# lcd_arduino_alarm_clock.net
KiCad netlist of a schematic drawn in EAGLE
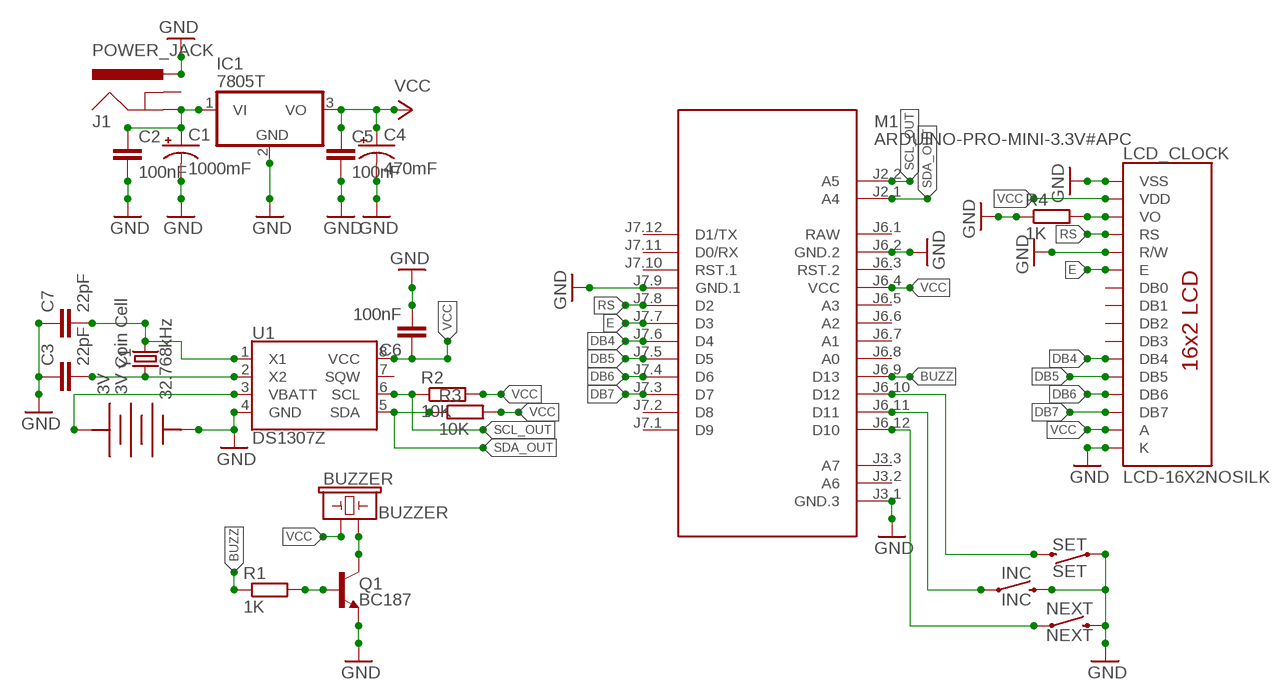
[diagram p0: schematic, sheet 1]

(export (version "E")
  (design (tool "Eeschema 10.0.6"))
  (components
    (comp (ref "3V")
      (value "3V Coin Cell")
      (footprint "eagle-import:FKIT-LIR2450-H")
      (libsource (lib "eagle-import") (part "FKIT-COIN_CELLLIR2450-H"))
    )
    (comp (ref "BUZZER")
      (value "BUZZER")
      (footprint "eagle-import:BUZZER-12MM")
      (libsource (lib "eagle-import") (part "BUZZER-PTH"))
    )
    (comp (ref "C1")
      (value "1000mF")
      (footprint "eagle-import:CPOL-RADIAL-5MM-10MM")
      (libsource (lib "eagle-import") (part "1000UF-RADIAL-5MM-25V-20%"))
    )
    (comp (ref "C2")
      (value "100nF")
      (footprint "eagle-import:0603")
      (libsource (lib "eagle-import") (part "100PF-0603-50V-5%"))
    )
    (comp (ref "C3")
      (value "22pF")
      (footprint "eagle-import:0603")
      (libsource (lib "eagle-import") (part "100PF-0603-50V-5%"))
    )
    (comp (ref "C4")
      (value "470mF")
      (footprint "eagle-import:CPOL-RADIAL-5MM-10MM")
      (libsource (lib "eagle-import") (part "1000UF-RADIAL-5MM-25V-20%"))
    )
    (comp (ref "C5")
      (value "100nF")
      (footprint "eagle-import:0603")
      (libsource (lib "eagle-import") (part "100PF-0603-50V-5%"))
    )
    (comp (ref "C6")
      (value "100nF")
      (footprint "eagle-import:0603")
      (libsource (lib "eagle-import") (part "100PF-0603-50V-5%"))
    )
    (comp (ref "C7")
      (value "22pF")
      (footprint "eagle-import:0603")
      (libsource (lib "eagle-import") (part "100PF-0603-50V-5%"))
    )
    (comp (ref "IC1")
      (value "7805T")
      (footprint "eagle-import:TO220H")
      (libsource (lib "eagle-import") (part "78T05"))
    )
    (comp (ref "INC")
      (value "INC")
      (footprint "eagle-import:TACTILE_SWITCH_PTH_6.0MM")
      (libsource (lib "eagle-import") (part "MOMENTARY-SWITCH-SPST-PTH-6.0MM"))
    )
    (comp (ref "J1")
      (value "POWER_JACK")
      (footprint "eagle-import:POWER_JACK_PTH")
      (libsource (lib "eagle-import") (part "POWER_JACK"))
    )
    (comp (ref "LCD_CLOCK")
      (value "LCD-16X2NOSILK")
      (footprint "eagle-import:LCD-16X2_NOSILK")
      (libsource (lib "eagle-import") (part "LCD-16X2NOSILK"))
    )
    (comp (ref "M1")
      (value "ARDUINO-PRO-MINI-3.3V#APC")
      (footprint "eagle-import:ARDUINO-PRO-MINI#APC")
      (libsource (lib "eagle-import") (part "ARDUINO-PRO-MINI-#APC3.3V"))
    )
    (comp (ref "NEXT")
      (value "NEXT")
      (footprint "eagle-import:TACTILE_SWITCH_PTH_6.0MM")
      (libsource (lib "eagle-import") (part "MOMENTARY-SWITCH-SPST-PTH-6.0MM"))
    )
    (comp (ref "Q1")
      (value "BC187")
      (footprint "eagle-import:TO-92")
      (libsource (lib "eagle-import") (part "TRANS_NPN-2N3904"))
    )
    (comp (ref "R1")
      (value "1K")
      (footprint "eagle-import:0204_5")
      (libsource (lib "eagle-import") (part "R-EU_0204/5"))
    )
    (comp (ref "R2")
      (value "10K")
      (footprint "eagle-import:0204_5")
      (libsource (lib "eagle-import") (part "R-EU_0204/5"))
    )
    (comp (ref "R3")
      (value "10K")
      (footprint "eagle-import:0204_5")
      (libsource (lib "eagle-import") (part "R-EU_0204/5"))
    )
    (comp (ref "R4")
      (value "1K")
      (footprint "eagle-import:0204_5")
      (libsource (lib "eagle-import") (part "R-EU_0204/5"))
    )
    (comp (ref "SET")
      (value "SET")
      (footprint "eagle-import:TACTILE_SWITCH_PTH_6.0MM")
      (libsource (lib "eagle-import") (part "MOMENTARY-SWITCH-SPST-PTH-6.0MM"))
    )
    (comp (ref "U1")
      (value "DS1307Z")
      (footprint "eagle-import:SO08-0.15")
      (libsource (lib "eagle-import") (part "DS1307Z"))
    )
    (comp (ref "Y1")
      (value "32.768kHz")
      (footprint "eagle-import:CRYSTAL-PTH-2X6-CYL")
      (libsource (lib "eagle-import") (part "CRYSTAL-32.768KHZPTH-2X6"))
    )
  )
  (nets
    (net (code "1") (name "/RAW") (class "Default")
      (node (ref "M1") (pin "J6.1") (pinfunction "RAW_J6.1") (pintype "power_in"))
    )
    (net (code "2") (name "BUZZ") (class "Default")
      (node (ref "M1") (pin "J6.9") (pinfunction "D13_J6.9") (pintype "bidirectional"))
      (node (ref "R1") (pin "1") (pinfunction "1_1") (pintype "passive"))
    )
    (net (code "3") (name "DB4") (class "Default")
      (node (ref "LCD_CLOCK") (pin "11") (pinfunction "DB4_11") (pintype "bidirectional"))
      (node (ref "M1") (pin "J7.6") (pinfunction "D4_J7.6") (pintype "bidirectional"))
    )
    (net (code "4") (name "DB5") (class "Default")
      (node (ref "LCD_CLOCK") (pin "12") (pinfunction "DB5_12") (pintype "bidirectional"))
      (node (ref "M1") (pin "J7.5") (pinfunction "D5_J7.5") (pintype "bidirectional"))
    )
    (net (code "5") (name "DB6") (class "Default")
      (node (ref "LCD_CLOCK") (pin "13") (pinfunction "DB6_13") (pintype "bidirectional"))
      (node (ref "M1") (pin "J7.4") (pinfunction "D6_J7.4") (pintype "bidirectional"))
    )
    (net (code "6") (name "DB7") (class "Default")
      (node (ref "LCD_CLOCK") (pin "14") (pinfunction "DB7_14") (pintype "bidirectional"))
      (node (ref "M1") (pin "J7.3") (pinfunction "D7_J7.3") (pintype "bidirectional"))
    )
    (net (code "7") (name "E") (class "Default")
      (node (ref "LCD_CLOCK") (pin "6") (pinfunction "E_6") (pintype "input"))
      (node (ref "M1") (pin "J7.7") (pinfunction "D3_J7.7") (pintype "bidirectional"))
    )
    (net (code "8") (name "GND") (class "Default")
      (node (ref "3V") (pin "NEG") (pinfunction "NEG_NEG") (pintype "bidirectional"))
      (node (ref "C1") (pin "-") (pinfunction "-_-") (pintype "passive"))
      (node (ref "C2") (pin "2") (pinfunction "2_2") (pintype "passive"))
      (node (ref "C3") (pin "1") (pinfunction "1_1") (pintype "passive"))
      (node (ref "C4") (pin "-") (pinfunction "-_-") (pintype "passive"))
      (node (ref "C5") (pin "2") (pinfunction "2_2") (pintype "passive"))
      (node (ref "C6") (pin "2") (pinfunction "2_2") (pintype "passive"))
      (node (ref "C7") (pin "1") (pinfunction "1_1") (pintype "passive"))
      (node (ref "IC1") (pin "2") (pinfunction "GND_2") (pintype "passive"))
      (node (ref "INC") (pin "3") (pinfunction "2_3") (pintype "passive"))
      (node (ref "J1") (pin "PWR") (pinfunction "PWR_PWR") (pintype "bidirectional"))
      (node (ref "LCD_CLOCK") (pin "1") (pinfunction "VSS_1") (pintype "power_in"))
      (node (ref "LCD_CLOCK") (pin "16") (pinfunction "K_16") (pintype "power_in"))
      (node (ref "LCD_CLOCK") (pin "5") (pinfunction "R/W_5") (pintype "input"))
      (node (ref "M1") (pin "J3.1") (pinfunction "GND.3_J3.1") (pintype "bidirectional"))
      (node (ref "M1") (pin "J6.2") (pinfunction "GND.2_J6.2") (pintype "power_in"))
      (node (ref "M1") (pin "J7.9") (pinfunction "GND.1_J7.9") (pintype "power_in"))
      (node (ref "NEXT") (pin "3") (pinfunction "2_3") (pintype "passive"))
      (node (ref "Q1") (pin "1") (pinfunction "E_1") (pintype "passive"))
      (node (ref "R4") (pin "1") (pinfunction "1_1") (pintype "passive"))
      (node (ref "SET") (pin "1") (pinfunction "1_1") (pintype "passive"))
      (node (ref "U1") (pin "4") (pinfunction "GND_4") (pintype "bidirectional"))
    )
    (net (code "9") (name "Net-(BUZZER-2)") (class "Default")
      (node (ref "BUZZER") (pin "-") (pinfunction "2_-") (pintype "passive"))
      (node (ref "Q1") (pin "3") (pinfunction "C_3") (pintype "passive"))
    )
    (net (code "10") (name "Net-(IC1-VI)") (class "Default")
      (node (ref "C1") (pin "+") (pinfunction "+_+") (pintype "passive"))
      (node (ref "C2") (pin "1") (pinfunction "1_1") (pintype "passive"))
      (node (ref "IC1") (pin "1") (pinfunction "VI_1") (pintype "input"))
      (node (ref "J1") (pin "GND") (pinfunction "GND_GND") (pintype "bidirectional"))
    )
    (net (code "11") (name "Net-(LCD_CLOCK-VO)") (class "Default")
      (node (ref "LCD_CLOCK") (pin "3") (pinfunction "VO_3") (pintype "bidirectional"))
      (node (ref "R4") (pin "2") (pinfunction "2_2") (pintype "passive"))
    )
    (net (code "12") (name "Net-(M1-D10)") (class "Default")
      (node (ref "M1") (pin "J6.12") (pinfunction "D10_J6.12") (pintype "bidirectional"))
      (node (ref "NEXT") (pin "1") (pinfunction "1_1") (pintype "passive"))
    )
    (net (code "13") (name "Net-(M1-D11)") (class "Default")
      (node (ref "INC") (pin "1") (pinfunction "1_1") (pintype "passive"))
      (node (ref "M1") (pin "J6.11") (pinfunction "D11_J6.11") (pintype "bidirectional"))
    )
    (net (code "14") (name "Net-(M1-D12)") (class "Default")
      (node (ref "M1") (pin "J6.10") (pinfunction "D12_J6.10") (pintype "bidirectional"))
      (node (ref "SET") (pin "3") (pinfunction "2_3") (pintype "passive"))
    )
    (net (code "15") (name "Net-(Q1-B)") (class "Default")
      (node (ref "Q1") (pin "2") (pinfunction "B_2") (pintype "passive"))
      (node (ref "R1") (pin "2") (pinfunction "2_2") (pintype "passive"))
    )
    (net (code "16") (name "Net-(U1-VBATT)") (class "Default")
      (node (ref "3V") (pin "POS") (pinfunction "POS_POS") (pintype "bidirectional"))
      (node (ref "U1") (pin "3") (pinfunction "VBATT_3") (pintype "bidirectional"))
    )
    (net (code "17") (name "Net-(U1-X1)") (class "Default")
      (node (ref "C7") (pin "2") (pinfunction "2_2") (pintype "passive"))
      (node (ref "U1") (pin "1") (pinfunction "X1_1") (pintype "bidirectional"))
      (node (ref "Y1") (pin "2") (pinfunction "2_2") (pintype "passive"))
    )
    (net (code "18") (name "Net-(U1-X2)") (class "Default")
      (node (ref "C3") (pin "2") (pinfunction "2_2") (pintype "passive"))
      (node (ref "U1") (pin "2") (pinfunction "X2_2") (pintype "bidirectional"))
      (node (ref "Y1") (pin "1") (pinfunction "1_1") (pintype "passive"))
    )
    (net (code "19") (name "RS") (class "Default")
      (node (ref "LCD_CLOCK") (pin "4") (pinfunction "RS_4") (pintype "input"))
      (node (ref "M1") (pin "J7.8") (pinfunction "D2_J7.8") (pintype "bidirectional"))
    )
    (net (code "20") (name "SCL_OUT") (class "Default")
      (node (ref "M1") (pin "J2.2") (pinfunction "A5_J2.2") (pintype "bidirectional"))
      (node (ref "R2") (pin "1") (pinfunction "1_1") (pintype "passive"))
      (node (ref "U1") (pin "6") (pinfunction "SCL_6") (pintype "bidirectional"))
    )
    (net (code "21") (name "SDA_OUT") (class "Default")
      (node (ref "M1") (pin "J2.1") (pinfunction "A4_J2.1") (pintype "bidirectional"))
      (node (ref "R3") (pin "1") (pinfunction "1_1") (pintype "passive"))
      (node (ref "U1") (pin "5") (pinfunction "SDA_5") (pintype "bidirectional"))
    )
    (net (code "22") (name "VCC") (class "Default")
      (node (ref "BUZZER") (pin "+") (pinfunction "1_+") (pintype "passive"))
      (node (ref "C4") (pin "+") (pinfunction "+_+") (pintype "passive"))
      (node (ref "C5") (pin "1") (pinfunction "1_1") (pintype "passive"))
      (node (ref "C6") (pin "1") (pinfunction "1_1") (pintype "passive"))
      (node (ref "IC1") (pin "3") (pinfunction "VO_3") (pintype "passive"))
      (node (ref "LCD_CLOCK") (pin "15") (pinfunction "A_15") (pintype "power_in"))
      (node (ref "LCD_CLOCK") (pin "2") (pinfunction "VDD_2") (pintype "power_in"))
      (node (ref "M1") (pin "J6.4") (pinfunction "VCC_J6.4") (pintype "power_in"))
      (node (ref "R2") (pin "2") (pinfunction "2_2") (pintype "passive"))
      (node (ref "R3") (pin "2") (pinfunction "2_2") (pintype "passive"))
      (node (ref "U1") (pin "8") (pinfunction "VCC_8") (pintype "bidirectional"))
    )
    (net (code "23") (name "unconnected-(J1-PadGNDBREAK)") (class "Default")
      (node (ref "J1") (pin "GNDBREAK") (pinfunction "GNDBREAK_GNDBREAK") (pintype "bidirectional"))
    )
    (net (code "24") (name "unconnected-(LCD_CLOCK-DB0-Pad7)") (class "Default")
      (node (ref "LCD_CLOCK") (pin "7") (pinfunction "DB0_7") (pintype "bidirectional"))
    )
    (net (code "25") (name "unconnected-(LCD_CLOCK-DB1-Pad8)") (class "Default")
      (node (ref "LCD_CLOCK") (pin "8") (pinfunction "DB1_8") (pintype "bidirectional"))
    )
    (net (code "26") (name "unconnected-(LCD_CLOCK-DB2-Pad9)") (class "Default")
      (node (ref "LCD_CLOCK") (pin "9") (pinfunction "DB2_9") (pintype "bidirectional"))
    )
    (net (code "27") (name "unconnected-(LCD_CLOCK-DB3-Pad10)") (class "Default")
      (node (ref "LCD_CLOCK") (pin "10") (pinfunction "DB3_10") (pintype "bidirectional"))
    )
    (net (code "28") (name "unconnected-(M1-A0-PadJ6.8)") (class "Default")
      (node (ref "M1") (pin "J6.8") (pinfunction "A0_J6.8") (pintype "bidirectional"))
    )
    (net (code "29") (name "unconnected-(M1-A1-PadJ6.7)") (class "Default")
      (node (ref "M1") (pin "J6.7") (pinfunction "A1_J6.7") (pintype "bidirectional"))
    )
    (net (code "30") (name "unconnected-(M1-A2-PadJ6.6)") (class "Default")
      (node (ref "M1") (pin "J6.6") (pinfunction "A2_J6.6") (pintype "bidirectional"))
    )
    (net (code "31") (name "unconnected-(M1-A3-PadJ6.5)") (class "Default")
      (node (ref "M1") (pin "J6.5") (pinfunction "A3_J6.5") (pintype "bidirectional"))
    )
    (net (code "32") (name "unconnected-(M1-A6-PadJ3.2)") (class "Default")
      (node (ref "M1") (pin "J3.2") (pinfunction "A6_J3.2") (pintype "bidirectional"))
    )
    (net (code "33") (name "unconnected-(M1-A7-PadJ3.3)") (class "Default")
      (node (ref "M1") (pin "J3.3") (pinfunction "A7_J3.3") (pintype "bidirectional"))
    )
    (net (code "34") (name "unconnected-(M1-D0{slash}RX-PadJ7.11)") (class "Default")
      (node (ref "M1") (pin "J7.11") (pinfunction "D0/RX_J7.11") (pintype "bidirectional"))
    )
    (net (code "35") (name "unconnected-(M1-D1{slash}TX-PadJ7.12)") (class "Default")
      (node (ref "M1") (pin "J7.12") (pinfunction "D1/TX_J7.12") (pintype "bidirectional"))
    )
    (net (code "36") (name "unconnected-(M1-D8-PadJ7.2)") (class "Default")
      (node (ref "M1") (pin "J7.2") (pinfunction "D8_J7.2") (pintype "bidirectional"))
    )
    (net (code "37") (name "unconnected-(M1-D9-PadJ7.1)") (class "Default")
      (node (ref "M1") (pin "J7.1") (pinfunction "D9_J7.1") (pintype "bidirectional"))
    )
    (net (code "38") (name "unconnected-(M1-RST.1-PadJ7.10)") (class "Default")
      (node (ref "M1") (pin "J7.10") (pinfunction "RST.1_J7.10") (pintype "bidirectional"))
    )
    (net (code "39") (name "unconnected-(M1-RST.2-PadJ6.3)") (class "Default")
      (node (ref "M1") (pin "J6.3") (pinfunction "RST.2_J6.3") (pintype "bidirectional"))
    )
    (net (code "40") (name "unconnected-(U1-SQW-Pad7)") (class "Default")
      (node (ref "U1") (pin "7") (pinfunction "SQW_7") (pintype "bidirectional"))
    )
  )
)
